# PROC010C_CAN_Interface.net
KiCad netlist of a schematic drawn in Altium Designer
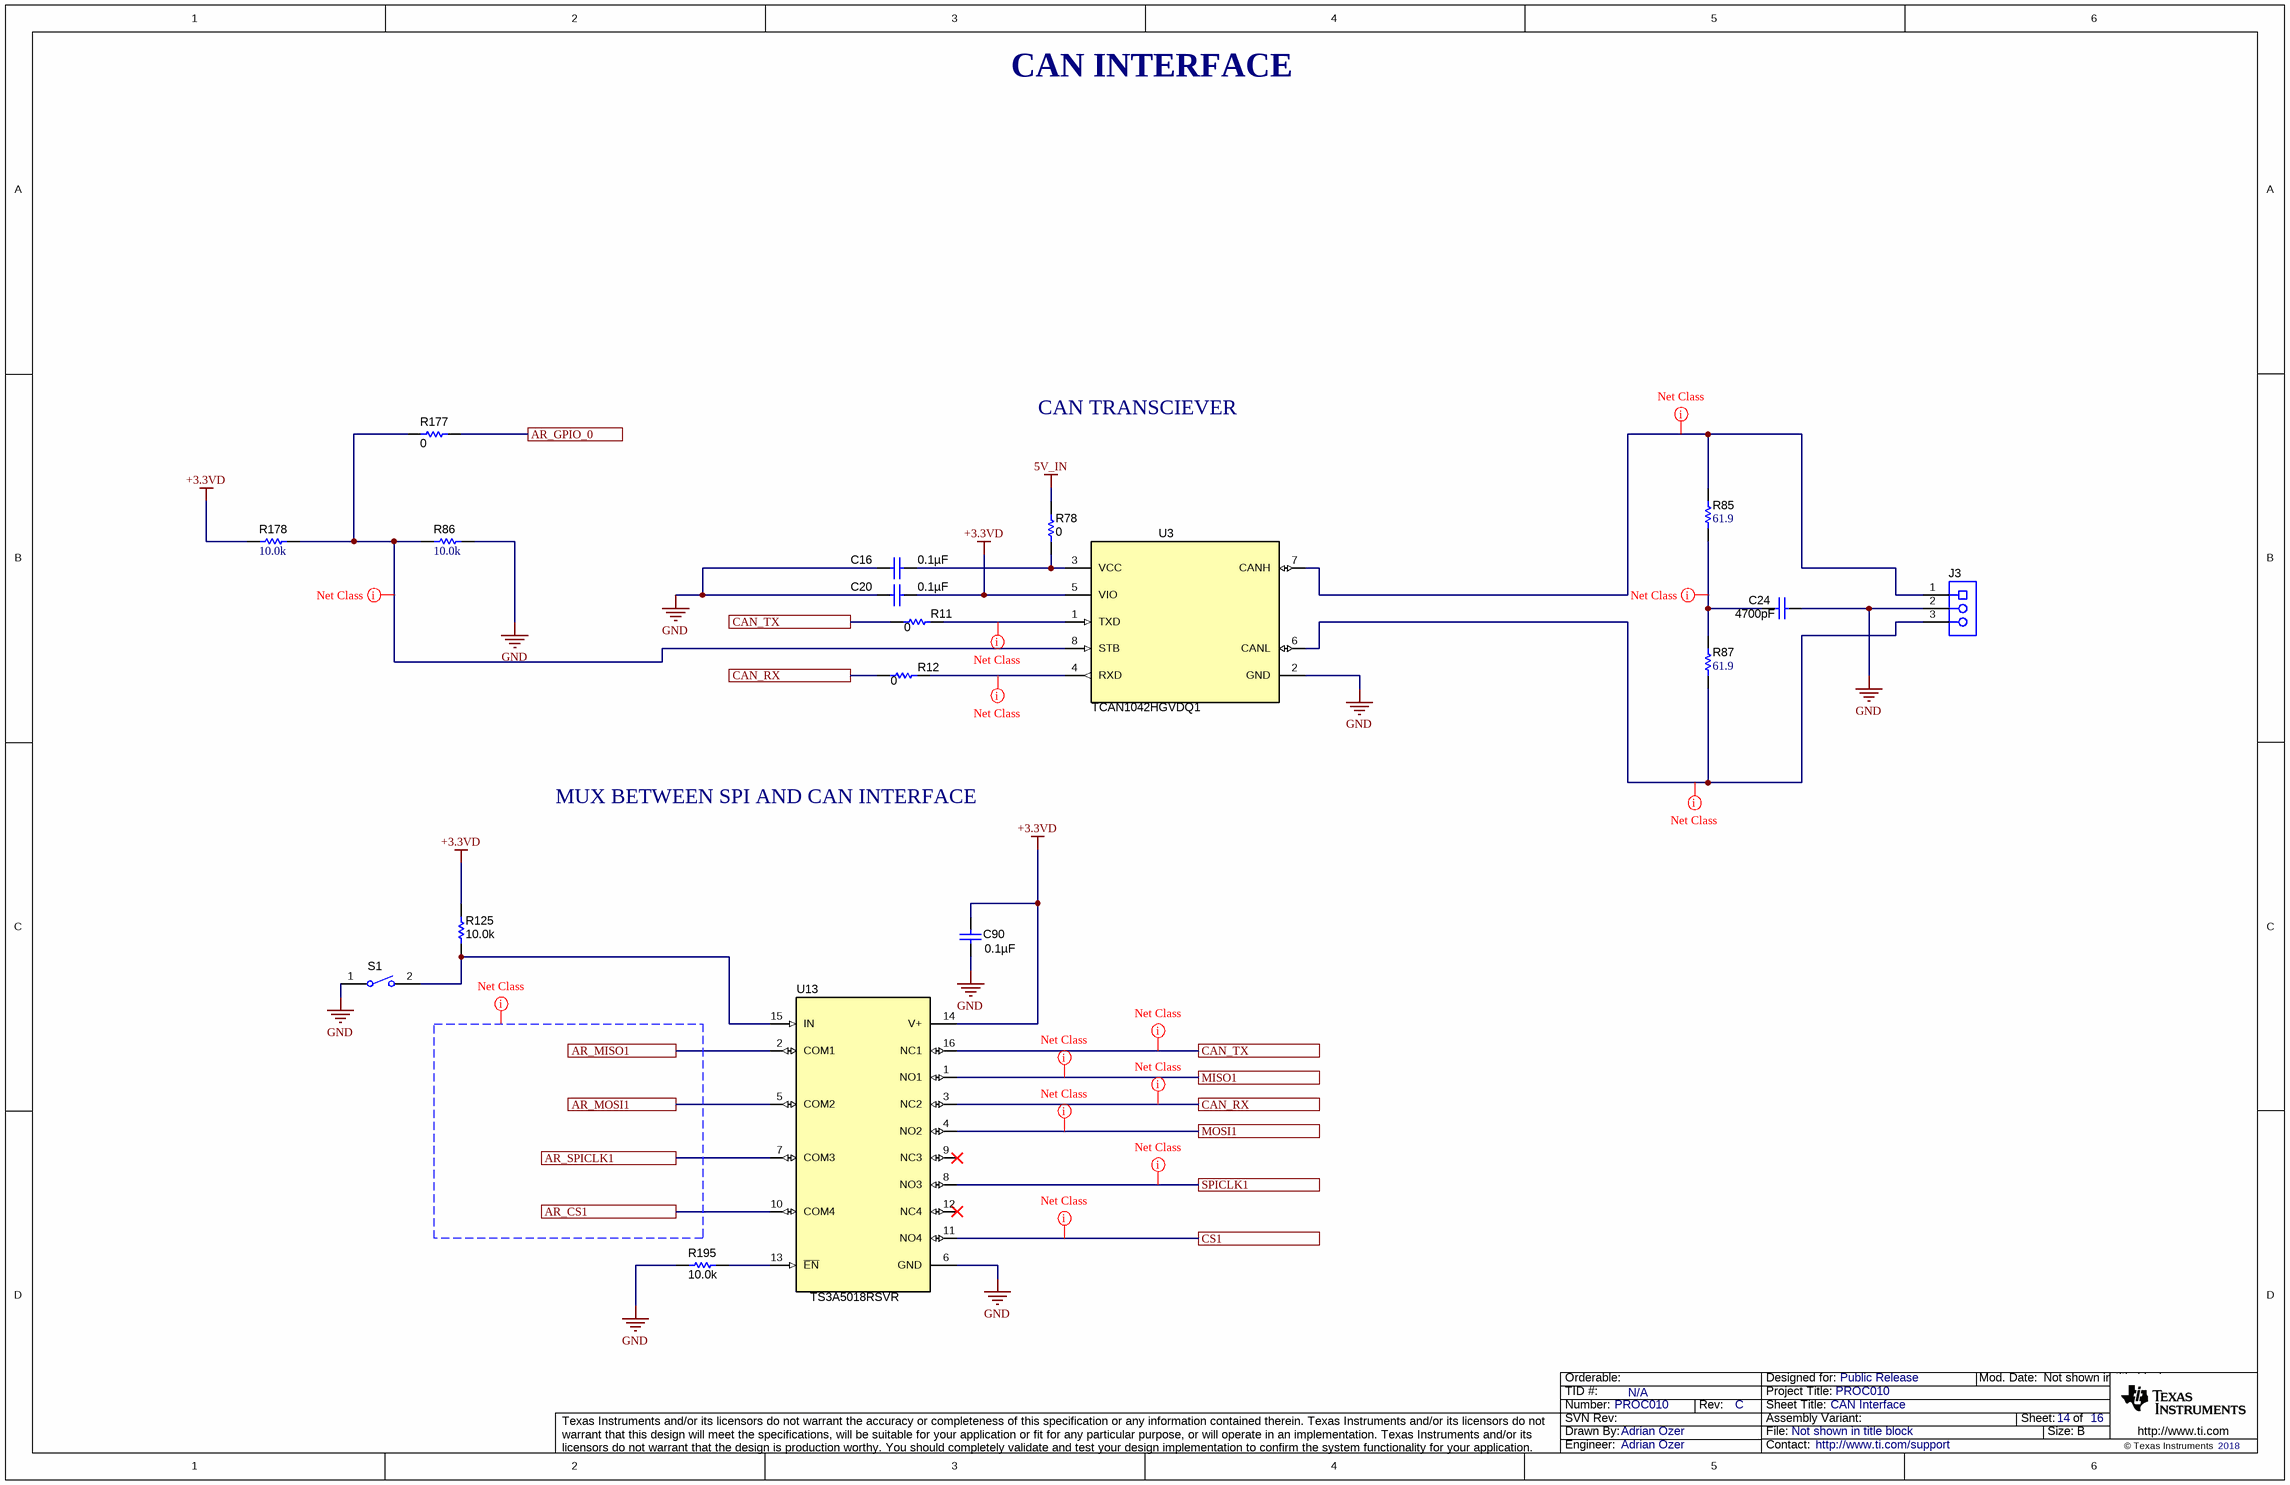
[diagram p0: PROC010C_CAN Interface.SchDoc]

(export (version "E")
  (design (tool "Eeschema 10.0.6"))
  (components
    (comp (ref "C16")
      (value "C0402C104K8RACTU")
      (footprint "0402L")
      (description "CAP, CERM, 0.1 µF, 10 V,+/- 10%, X7R, 0402")
      (fields (field (name "MANUFACTURER") "Kemet") (field (name "VALUEDISPLAYED") "0.1µF"))
      (libsource (lib "Altium Vault - TI") (part "Capacitor"))
    )
    (comp (ref "C20")
      (value "C0402C104K8RACTU")
      (footprint "0402L")
      (description "CAP, CERM, 0.1 µF, 10 V,+/- 10%, X7R, 0402")
      (fields (field (name "MANUFACTURER") "Kemet") (field (name "VALUEDISPLAYED") "0.1µF"))
      (libsource (lib "Altium Vault - TI") (part "Capacitor"))
    )
    (comp (ref "C24")
      (value "C1005X7R1H472K050BA")
      (footprint "0402L")
      (description "CAP, CERM, 4700 pF, 50 V,+/- 10%, X7R, 0402")
      (fields (field (name "MANUFACTURER") "TDK") (field (name "VALUEDISPLAYED") "4700pF"))
      (libsource (lib "Altium Vault - TI") (part "Capacitor"))
    )
    (comp (ref "C90")
      (value "C0402C104K8RACTU")
      (footprint "0402L")
      (description "CAP, CERM, 0.1 µF, 10 V,+/- 10%, X7R, 0402")
      (fields (field (name "MANUFACTURER") "Kemet") (field (name "VALUEDISPLAYED") "0.1µF"))
      (libsource (lib "Altium Vault - TI") (part "Capacitor"))
    )
    (comp (ref "J3")
      (value "OSTTE030161")
      (footprint "On-Shore_OSTTE030161")
      (description "Terminal Block, 3.5mm, 3x1, Tin, R/A, TH")
      (fields
        (field (name "MANUFACTURER") "On-Shore Technology")
        (field (name "PUBLISHER") "Texas Instruments")
      )
      (libsource (lib "Altium Vault - TI") (part "Receptacle_3x1"))
    )
    (comp (ref "R11")
      (value "ERJ-2GE0R00X")
      (footprint "0402L")
      (description "RES, 0, 5%, 0.063 W, 0402")
      (fields
        (field (name "MANUFACTURER") "Panasonic")
        (field (name "VALUEDISPLAYED") "0")
        (field (name "PUBLISHER") "Texas Instruments")
      )
      (libsource (lib "Altium Vault - TI") (part "CMP-0026992-2"))
    )
    (comp (ref "R12")
      (value "ERJ-2GE0R00X")
      (footprint "0402L")
      (description "RES, 0, 5%, 0.063 W, 0402")
      (fields
        (field (name "MANUFACTURER") "Panasonic")
        (field (name "VALUEDISPLAYED") "0")
        (field (name "PUBLISHER") "Texas Instruments")
      )
      (libsource (lib "Altium Vault - TI") (part "CMP-0026992-2"))
    )
    (comp (ref "R78")
      (value "ERJ-2GE0R00X")
      (footprint "0402L")
      (description "RES, 0, 5%, 0.063 W, 0402")
      (fields
        (field (name "MANUFACTURER") "Panasonic")
        (field (name "VALUEDISPLAYED") "0")
        (field (name "PUBLISHER") "Texas Instruments")
      )
      (libsource (lib "Altium Vault - TI") (part "CMP-0026992-2"))
    )
    (comp (ref "R85")
      (value "CRCW040261R9FKED")
      (footprint "0402L")
      (description "RES, 61.9, 1%, 0.063 W, AEC-Q200 Grade 0, 0402")
      (fields (field (name "MANUFACTURER") "Vishay-Dale") (field (name "VALUEDISPLAYED") "61.9"))
      (libsource (lib "Altium Vault - TI") (part "Resistor"))
    )
    (comp (ref "R86")
      (value "CRCW040210K0FKED")
      (footprint "0402L")
      (description "RES, 10.0 k, 1%, 0.063 W, AEC-Q200 Grade 0, 0402")
      (fields (field (name "MANUFACTURER") "Vishay-Dale") (field (name "VALUEDISPLAYED") "10.0k"))
      (libsource (lib "Altium Vault - TI") (part "Resistor"))
    )
    (comp (ref "R87")
      (value "CRCW040261R9FKED")
      (footprint "0402L")
      (description "RES, 61.9, 1%, 0.063 W, AEC-Q200 Grade 0, 0402")
      (fields (field (name "MANUFACTURER") "Vishay-Dale") (field (name "VALUEDISPLAYED") "61.9"))
      (libsource (lib "Altium Vault - TI") (part "Resistor"))
    )
    (comp (ref "R125")
      (value "CRCW040210K0FKED")
      (footprint "0402L")
      (description "RES, 10.0 k, 1%, 0.063 W, 0402")
      (fields
        (field (name "MANUFACTURER") "Vishay-Dale")
        (field (name "VALUEDISPLAYED") "10.0k")
        (field (name "PUBLISHER") "Texas Instruments")
      )
      (libsource (lib "Altium Vault - TI") (part "CMP-0025958-2"))
    )
    (comp (ref "R177")
      (value "ERJ-2GE0R00X")
      (footprint "0402L")
      (description "RES, 0, 5%, 0.063 W, 0402")
      (fields
        (field (name "MANUFACTURER") "Panasonic")
        (field (name "VALUEDISPLAYED") "0")
        (field (name "PUBLISHER") "Texas Instruments")
      )
      (libsource (lib "Altium Vault - TI") (part "CMP-0026992-2"))
    )
    (comp (ref "R178")
      (value "CRCW040210K0FKED")
      (footprint "0402L")
      (description "RES, 10.0 k, 1%, 0.063 W, AEC-Q200 Grade 0, 0402")
      (fields (field (name "MANUFACTURER") "Vishay-Dale") (field (name "VALUEDISPLAYED") "10.0k"))
      (libsource (lib "Altium Vault - TI") (part "Resistor"))
    )
    (comp (ref "R195")
      (value "CRCW040210K0FKED")
      (footprint "0402L")
      (description "RES, 10.0 k, 1%, 0.063 W, 0402")
      (fields
        (field (name "MANUFACTURER") "Vishay-Dale")
        (field (name "VALUEDISPLAYED") "10.0k")
        (field (name "PUBLISHER") "Texas Instruments")
      )
      (libsource (lib "Altium Vault - TI") (part "CMP-0025958-2"))
    )
    (comp (ref "S1")
      (value "CHS-01TB")
      (footprint "SW_CHS-01TB")
      (description "Switch, Slide, SPST, Top Slide, SMT")
      (fields
        (field (name "MANUFACTURER") "Copal Electronics")
        (field (name "PUBLISHER") "Texas Instruments")
      )
      (libsource (lib "Altium Vault - TI") (part "SW_SPST-single"))
    )
    (comp (ref "U3")
      (value "TCAN1042HGVDQ1")
      (footprint "D0008A_L")
      (description "Automotive Fault Protected CAN Transceiver With Flexible Data-Rate, D0008A (SOIC-8)")
      (fields
        (field (name "PARTNUMBER") "TCAN1042HGVDQ1")
        (field (name "MANUFACTURER") "Texas Instruments")
        (field (name "ALTERNATE PARTNUMBER") "TCAN1042HGVDRQ1")
        (field (name "PUBLISHER") "Texas Instruments")
      )
      (libsource (lib "Altium Vault - TI") (part "TCAN1042_V"))
    )
    (comp (ref "U13")
      (value "TS3A5018RSVR")
      (footprint "RSV0016A")
      (description "10-Ohm Quad SPDT Analog Switch, RSV0016A (UQFN-16)")
      (fields
        (field (name "MANUFACTURER") "Texas Instruments")
        (field (name "PARTNUMBER") "TS3A5018RSVR")
        (field (name "PUBLISHER") "Texas Instruments")
      )
      (libsource (lib "Altium Vault - TI") (part "CMP-0067415-1"))
    )
  )
  (nets
    (net (code "1") (name "+3.3VD") (class "Default")
      (node (ref "C20") (pin "2") (pinfunction "2_2") (pintype "passive"))
      (node (ref "C90") (pin "2") (pinfunction "2_2") (pintype "passive"))
      (node (ref "R125") (pin "2") (pinfunction "2_2") (pintype "passive"))
      (node (ref "R178") (pin "1") (pinfunction "1_1") (pintype "passive"))
      (node (ref "U13") (pin "14") (pinfunction "V+_14") (pintype "power_in"))
      (node (ref "U3") (pin "5") (pinfunction "VIO_5") (pintype "power_in"))
    )
    (net (code "2") (name "/AR_CS1") (class "Default")
      (node (ref "U13") (pin "10") (pinfunction "COM4_10") (pintype "bidirectional"))
    )
    (net (code "3") (name "/AR_GPIO_0") (class "Default")
      (node (ref "R177") (pin "2") (pinfunction "2_2") (pintype "passive"))
    )
    (net (code "4") (name "/AR_MISO1") (class "Default")
      (node (ref "U13") (pin "2") (pinfunction "COM1_2") (pintype "bidirectional"))
    )
    (net (code "5") (name "/AR_MOSI1") (class "Default")
      (node (ref "U13") (pin "5") (pinfunction "COM2_5") (pintype "bidirectional"))
    )
    (net (code "6") (name "/AR_SPICLK1") (class "Default")
      (node (ref "U13") (pin "7") (pinfunction "COM3_7") (pintype "bidirectional"))
    )
    (net (code "7") (name "/CAN_RX") (class "Default")
      (node (ref "R12") (pin "1") (pinfunction "1_1") (pintype "passive"))
      (node (ref "U13") (pin "3") (pinfunction "NC2_3") (pintype "bidirectional"))
    )
    (net (code "8") (name "/CAN_TX") (class "Default")
      (node (ref "R11") (pin "1") (pinfunction "1_1") (pintype "passive"))
      (node (ref "U13") (pin "16") (pinfunction "NC1_16") (pintype "bidirectional"))
    )
    (net (code "9") (name "/CS1") (class "Default")
      (node (ref "U13") (pin "11") (pinfunction "NO4_11") (pintype "bidirectional"))
    )
    (net (code "10") (name "/MISO1") (class "Default")
      (node (ref "U13") (pin "1") (pinfunction "NO1_1") (pintype "bidirectional"))
    )
    (net (code "11") (name "/MOSI1") (class "Default")
      (node (ref "U13") (pin "4") (pinfunction "NO2_4") (pintype "bidirectional"))
    )
    (net (code "12") (name "/SPICLK1") (class "Default")
      (node (ref "U13") (pin "8") (pinfunction "NO3_8") (pintype "bidirectional"))
    )
    (net (code "13") (name "5V_IN") (class "Default")
      (node (ref "R78") (pin "2") (pinfunction "2_2") (pintype "passive"))
    )
    (net (code "14") (name "GND") (class "Default")
      (node (ref "C16") (pin "1") (pinfunction "1_1") (pintype "passive"))
      (node (ref "C20") (pin "1") (pinfunction "1_1") (pintype "passive"))
      (node (ref "C24") (pin "1") (pinfunction "1_1") (pintype "passive"))
      (node (ref "C90") (pin "1") (pinfunction "1_1") (pintype "passive"))
      (node (ref "J3") (pin "2") (pinfunction "2_2") (pintype "passive"))
      (node (ref "R195") (pin "2") (pinfunction "2_2") (pintype "passive"))
      (node (ref "R86") (pin "2") (pinfunction "2_2") (pintype "passive"))
      (node (ref "S1") (pin "1") (pinfunction "1_1") (pintype "passive"))
      (node (ref "U13") (pin "6") (pinfunction "GND_6") (pintype "power_in"))
      (node (ref "U3") (pin "2") (pinfunction "GND_2") (pintype "power_in"))
    )
    (net (code "15") (name "Net-(C24-Pad2)") (class "Default")
      (node (ref "C24") (pin "2") (pinfunction "2_2") (pintype "passive"))
      (node (ref "R85") (pin "1") (pinfunction "1_1") (pintype "passive"))
      (node (ref "R87") (pin "2") (pinfunction "2_2") (pintype "passive"))
    )
    (net (code "16") (name "Net-(U3-CANH)") (class "Default")
      (node (ref "J3") (pin "1") (pinfunction "1_1") (pintype "passive"))
      (node (ref "R85") (pin "2") (pinfunction "2_2") (pintype "passive"))
      (node (ref "U3") (pin "7") (pinfunction "CANH_7") (pintype "bidirectional"))
    )
    (net (code "17") (name "Net-(U3-CANL)") (class "Default")
      (node (ref "J3") (pin "3") (pinfunction "3_3") (pintype "passive"))
      (node (ref "R87") (pin "1") (pinfunction "1_1") (pintype "passive"))
      (node (ref "U3") (pin "6") (pinfunction "CANL_6") (pintype "bidirectional"))
    )
    (net (code "18") (name "Net-(U3-RXD)") (class "Default")
      (node (ref "R12") (pin "2") (pinfunction "2_2") (pintype "passive"))
      (node (ref "U3") (pin "4") (pinfunction "RXD_4") (pintype "output"))
    )
    (net (code "19") (name "Net-(U3-STB)") (class "Default")
      (node (ref "R177") (pin "1") (pinfunction "1_1") (pintype "passive"))
      (node (ref "R178") (pin "2") (pinfunction "2_2") (pintype "passive"))
      (node (ref "R86") (pin "1") (pinfunction "1_1") (pintype "passive"))
      (node (ref "U3") (pin "8") (pinfunction "STB_8") (pintype "input"))
    )
    (net (code "20") (name "Net-(U3-TXD)") (class "Default")
      (node (ref "R11") (pin "2") (pinfunction "2_2") (pintype "passive"))
      (node (ref "U3") (pin "1") (pinfunction "TXD_1") (pintype "input"))
    )
    (net (code "21") (name "Net-(U3-VCC)") (class "Default")
      (node (ref "C16") (pin "2") (pinfunction "2_2") (pintype "passive"))
      (node (ref "R78") (pin "1") (pinfunction "1_1") (pintype "passive"))
      (node (ref "U3") (pin "3") (pinfunction "VCC_3") (pintype "power_in"))
    )
    (net (code "22") (name "Net-(U13-EN)") (class "Default")
      (node (ref "R195") (pin "1") (pinfunction "1_1") (pintype "passive"))
      (node (ref "U13") (pin "13") (pinfunction "EN_13") (pintype "input"))
    )
    (net (code "23") (name "Net-(U13-IN)") (class "Default")
      (node (ref "R125") (pin "1") (pinfunction "1_1") (pintype "passive"))
      (node (ref "S1") (pin "2") (pinfunction "2_2") (pintype "passive"))
      (node (ref "U13") (pin "15") (pinfunction "IN_15") (pintype "input"))
    )
    (net (code "24") (name "unconnected-(U13-NC3-Pad9)") (class "Default")
      (node (ref "U13") (pin "9") (pinfunction "NC3_9") (pintype "bidirectional+no_connect"))
    )
    (net (code "25") (name "unconnected-(U13-NC4-Pad12)") (class "Default")
      (node (ref "U13") (pin "12") (pinfunction "NC4_12") (pintype "bidirectional+no_connect"))
    )
  )
)
